# DC_DC_5V.net
KiCad netlist of a schematic drawn in Altium Designer
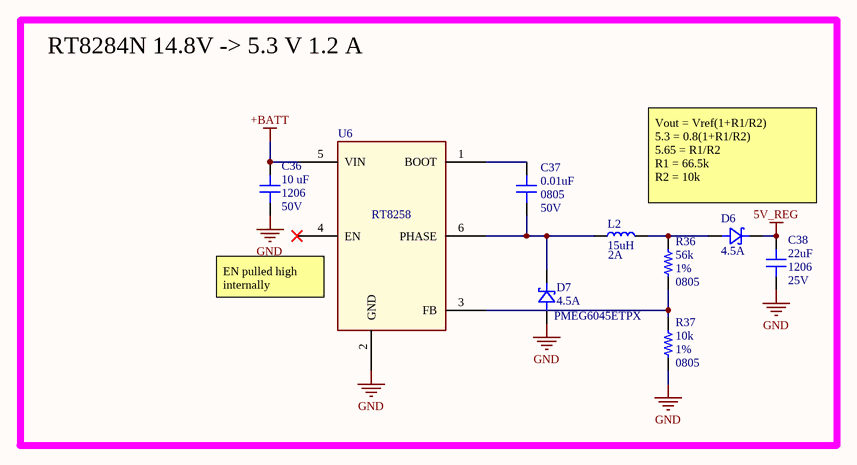
[diagram p0: DC_DC_5V.SchDoc]

(export (version "E")
  (design (tool "Eeschema 10.0.6"))
  (components
    (comp (ref "C36")
      (value "10 uF")
      (footprint "CAP_1206")
      (description "CAP - 1206")
      (fields
        (field (name "PACKAGE") "1206")
        (field (name "VOLTAGE") "50V")
        (field (name "PART NUMBER") "GRT31CR61H106ME01L")
      )
      (libsource (lib "SecureBot") (part "CAP - 1206"))
    )
    (comp (ref "C37")
      (value "0.01uF")
      (footprint "CAP_0805")
      (description "CAP - 0805")
      (fields
        (field (name "PART NUMBER") "CL21B103KBANNNC")
        (field (name "PACKAGE") "0805")
        (field (name "VOLTAGE") "50V")
      )
      (libsource (lib "SecureBot") (part "CAP - 0805"))
    )
    (comp (ref "C38")
      (value "22uF")
      (footprint "CAP_1206")
      (description "CAP - 1206")
      (fields
        (field (name "PART NUMBER") "CL31A226KAHNNNE")
        (field (name "PACKAGE") "1206")
        (field (name "VOLTAGE") "25V")
      )
      (libsource (lib "SecureBot") (part "CAP - 1206"))
    )
    (comp (ref "D6")
      (value "SCHOTTKEY")
      (footprint "DO-214AC_SOD128")
      (fields (field (name "CURRENT") "4.5A") (field (name "PART NUMBER") "PMEG6045ETPX"))
      (libsource (lib "SecureBot") (part "SCHOTTKEY"))
    )
    (comp (ref "D7")
      (value "SCHOTTKEY")
      (footprint "DO-214AC_SOD128")
      (fields (field (name "CURRENT") "4.5A") (field (name "PART NUMBER") "PMEG6045ETPX"))
      (libsource (lib "SecureBot") (part "SCHOTTKEY"))
    )
    (comp (ref "L2")
      (value "15uH")
      (footprint "NR5040T150M")
      (description "IND")
      (fields (field (name "CURRENT") "2A") (field (name "PART NUMBER") "NR5040T150M"))
      (libsource (lib "SecureBot") (part "IND"))
    )
    (comp (ref "R36")
      (value "56k")
      (footprint "FER_0805")
      (description "RES - 0805")
      (fields
        (field (name "TOLERANCE") "1%")
        (field (name "PACKAGE") "0805")
        (field (name "PART NUMBER") "RC0805FR-0756KL")
      )
      (libsource (lib "SecureBot") (part "RES - 0805"))
    )
    (comp (ref "R37")
      (value "10k")
      (footprint "FER_0805")
      (description "RES - 0805")
      (fields
        (field (name "TOLERANCE") "1%")
        (field (name "PACKAGE") "0805")
        (field (name "PART NUMBER") "RMCF0805FT10K0")
      )
      (libsource (lib "SecureBot") (part "RES - 0805"))
    )
    (comp (ref "U6") (value "RT8258") (footprint "SOT23-6") (libsource (lib "SecureBot") (part "RT8258")))
  )
  (nets
    (net (code "1") (name "+BATT") (class "Default")
      (node (ref "C36") (pin "1") (pinfunction "1_1") (pintype "passive"))
      (node (ref "U6") (pin "5") (pinfunction "VIN_5") (pintype "passive"))
    )
    (net (code "2") (name "5V_REG") (class "Default")
      (node (ref "C38") (pin "1") (pinfunction "1_1") (pintype "passive"))
      (node (ref "D6") (pin "2") (pinfunction "2_2") (pintype "passive"))
    )
    (net (code "3") (name "GND") (class "Default")
      (node (ref "C36") (pin "2") (pinfunction "2_2") (pintype "passive"))
      (node (ref "C38") (pin "2") (pinfunction "2_2") (pintype "passive"))
      (node (ref "D7") (pin "1") (pinfunction "1_1") (pintype "passive"))
      (node (ref "R37") (pin "2") (pinfunction "2_2") (pintype "passive"))
      (node (ref "U6") (pin "2") (pinfunction "GND_2") (pintype "passive"))
    )
    (net (code "4") (name "Net-(D6-Pad1)") (class "Default")
      (node (ref "D6") (pin "1") (pinfunction "1_1") (pintype "passive"))
      (node (ref "L2") (pin "2") (pinfunction "2_2") (pintype "passive"))
      (node (ref "R36") (pin "1") (pinfunction "1_1") (pintype "passive"))
    )
    (net (code "5") (name "Net-(U6-BOOT)") (class "Default")
      (node (ref "C37") (pin "1") (pinfunction "1_1") (pintype "passive"))
      (node (ref "U6") (pin "1") (pinfunction "BOOT_1") (pintype "passive"))
    )
    (net (code "6") (name "Net-(U6-FB)") (class "Default")
      (node (ref "R36") (pin "2") (pinfunction "2_2") (pintype "passive"))
      (node (ref "R37") (pin "1") (pinfunction "1_1") (pintype "passive"))
      (node (ref "U6") (pin "3") (pinfunction "FB_3") (pintype "passive"))
    )
    (net (code "7") (name "Net-(U6-PHASE)") (class "Default")
      (node (ref "C37") (pin "2") (pinfunction "2_2") (pintype "passive"))
      (node (ref "D7") (pin "2") (pinfunction "2_2") (pintype "passive"))
      (node (ref "L2") (pin "1") (pinfunction "1_1") (pintype "passive"))
      (node (ref "U6") (pin "6") (pinfunction "PHASE_6") (pintype "passive"))
    )
    (net (code "8") (name "unconnected-(U6-EN-Pad4)") (class "Default")
      (node (ref "U6") (pin "4") (pinfunction "EN_4") (pintype "passive+no_connect"))
    )
  )
)
